# GenericCommand.net
KiCad netlist of a schematic drawn in EAGLE
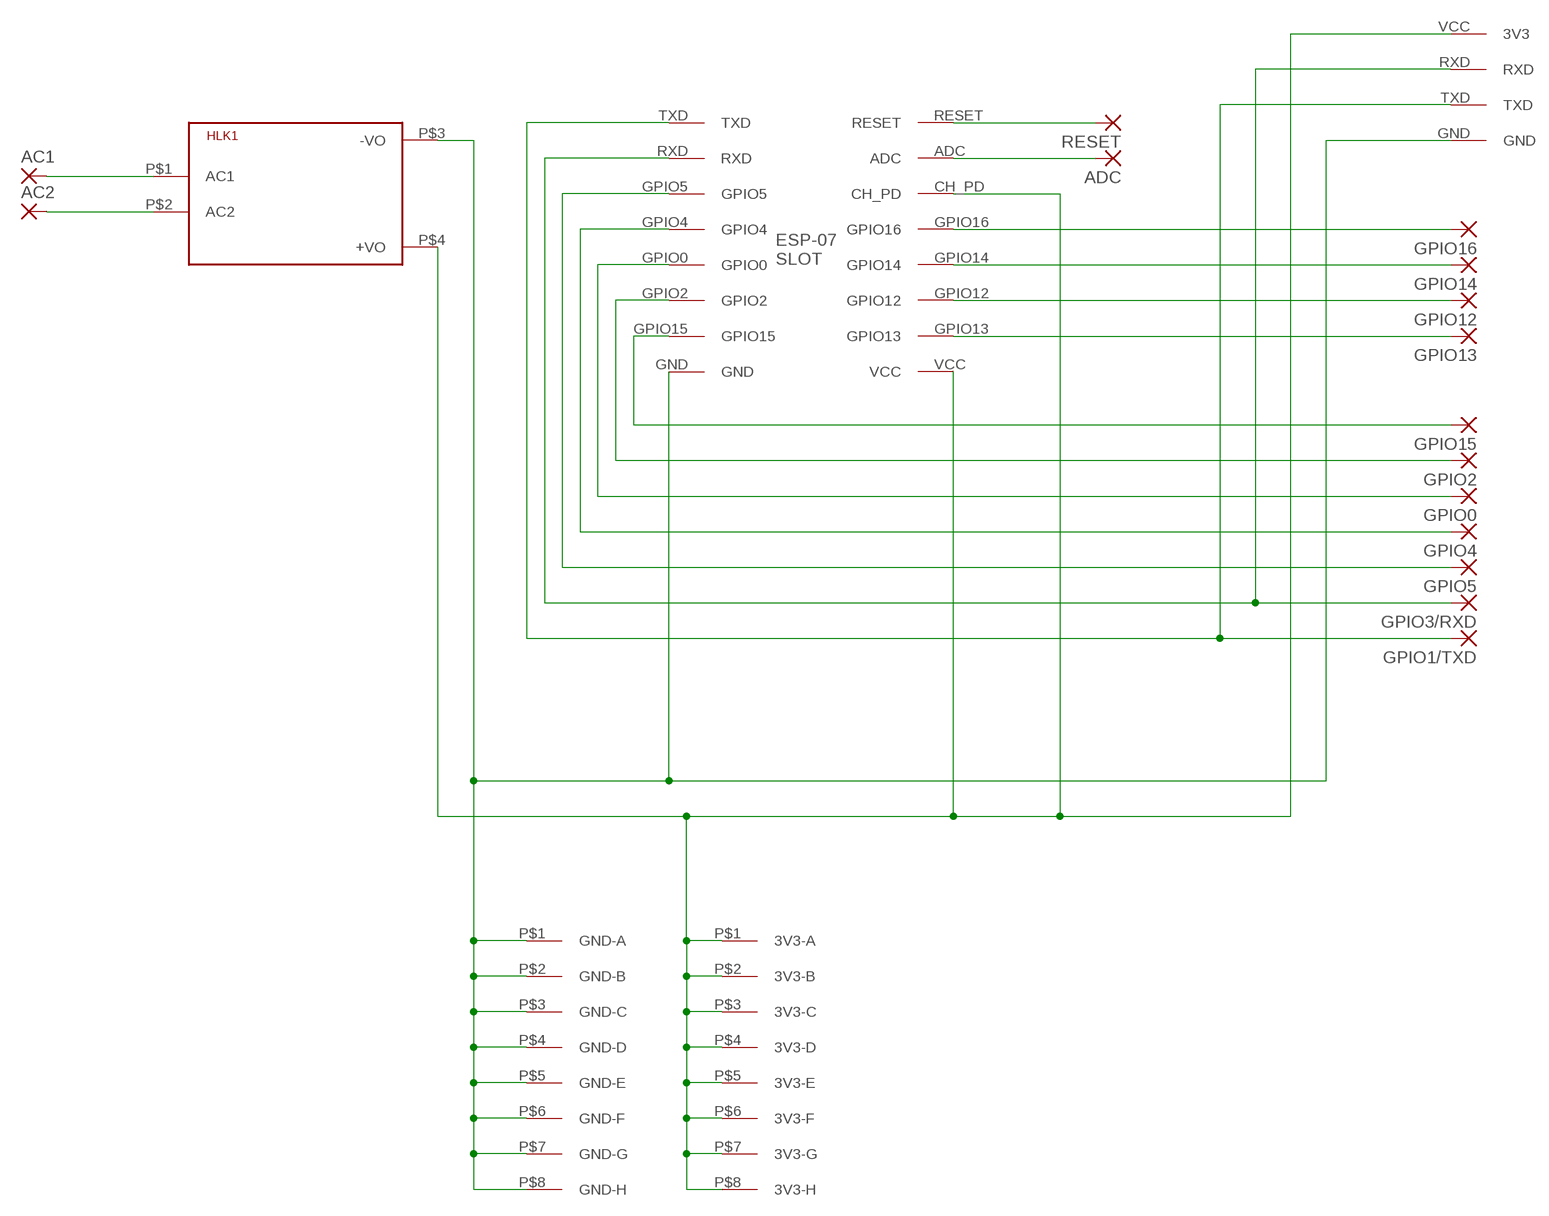
[diagram p0: schematic, sheet 1]

(export (version "E")
  (design (tool "Eeschema 10.0.6"))
  (components
    (comp (ref "AC1")
      (value "3,81/1,4")
      (footprint "eagle-import:3,81_1,4")
      (libsource (lib "eagle-import") (part "3,81/1,4"))
    )
    (comp (ref "AC2")
      (value "3,81/1,4")
      (footprint "eagle-import:3,81_1,4")
      (libsource (lib "eagle-import") (part "3,81/1,4"))
    )
    (comp (ref "ADC")
      (value "1,6/0,9")
      (footprint "eagle-import:1,6_0,9")
      (libsource (lib "eagle-import") (part "1,6/0,9"))
    )
    (comp (ref "GPIO0")
      (value "1,6/0,9")
      (footprint "eagle-import:1,6_0,9")
      (libsource (lib "eagle-import") (part "1,6/0,9"))
    )
    (comp (ref "GPIO1/TXD")
      (value "1,6/0,9")
      (footprint "eagle-import:1,6_0,9")
      (libsource (lib "eagle-import") (part "1,6/0,9"))
    )
    (comp (ref "GPIO2")
      (value "1,6/0,9")
      (footprint "eagle-import:1,6_0,9")
      (libsource (lib "eagle-import") (part "1,6/0,9"))
    )
    (comp (ref "GPIO3/RXD")
      (value "1,6/0,9")
      (footprint "eagle-import:1,6_0,9")
      (libsource (lib "eagle-import") (part "1,6/0,9"))
    )
    (comp (ref "GPIO4")
      (value "1,6/0,9")
      (footprint "eagle-import:1,6_0,9")
      (libsource (lib "eagle-import") (part "1,6/0,9"))
    )
    (comp (ref "GPIO5")
      (value "1,6/0,9")
      (footprint "eagle-import:1,6_0,9")
      (libsource (lib "eagle-import") (part "1,6/0,9"))
    )
    (comp (ref "GPIO12")
      (value "1,6/0,9")
      (footprint "eagle-import:1,6_0,9")
      (libsource (lib "eagle-import") (part "1,6/0,9"))
    )
    (comp (ref "GPIO13")
      (value "1,6/0,9")
      (footprint "eagle-import:1,6_0,9")
      (libsource (lib "eagle-import") (part "1,6/0,9"))
    )
    (comp (ref "GPIO14")
      (value "1,6/0,9")
      (footprint "eagle-import:1,6_0,9")
      (libsource (lib "eagle-import") (part "1,6/0,9"))
    )
    (comp (ref "GPIO15")
      (value "1,6/0,9")
      (footprint "eagle-import:1,6_0,9")
      (libsource (lib "eagle-import") (part "1,6/0,9"))
    )
    (comp (ref "GPIO16")
      (value "1,6/0,9")
      (footprint "eagle-import:1,6_0,9")
      (libsource (lib "eagle-import") (part "1,6/0,9"))
    )
    (comp (ref "HLK1")
      (value "HLK-PM013W")
      (footprint "eagle-import:HLK-PM01")
      (libsource (lib "eagle-import") (part "HLK-PM013W"))
    )
    (comp (ref "RESET")
      (value "1,6/0,9")
      (footprint "eagle-import:1,6_0,9")
      (libsource (lib "eagle-import") (part "1,6/0,9"))
    )
    (comp (ref "U$1")
      (value "ESP-07")
      (footprint "eagle-import:ESP-07")
      (libsource (lib "eagle-import") (part "ESP-07"))
    )
    (comp (ref "U$2")
      (value "CP-2102-CONN")
      (footprint "eagle-import:CP-2102-CONN")
      (libsource (lib "eagle-import") (part "CP-2102-CONN"))
    )
    (comp (ref "U$3")
      (value "3V3-8")
      (footprint "eagle-import:3.3V-8")
      (libsource (lib "eagle-import") (part "3V3-8"))
    )
    (comp (ref "U$4")
      (value "GND-8")
      (footprint "eagle-import:GND-8")
      (libsource (lib "eagle-import") (part "GND-8"))
    )
  )
  (nets
    (net (code "1") (name "Net-(AC1-P)") (class "Default")
      (node (ref "AC1") (pin "1") (pinfunction "P_1") (pintype "passive"))
      (node (ref "HLK1") (pin "P$1") (pinfunction "AC1_P$1") (pintype "bidirectional"))
    )
    (net (code "2") (name "Net-(AC2-P)") (class "Default")
      (node (ref "AC2") (pin "1") (pinfunction "P_1") (pintype "passive"))
      (node (ref "HLK1") (pin "P$2") (pinfunction "AC2_P$2") (pintype "bidirectional"))
    )
    (net (code "3") (name "Net-(ADC-P)") (class "Default")
      (node (ref "ADC") (pin "1") (pinfunction "P_1") (pintype "passive"))
      (node (ref "U$1") (pin "ADC") (pinfunction "ADC_ADC") (pintype "bidirectional"))
    )
    (net (code "4") (name "Net-(GPIO0-P)") (class "Default")
      (node (ref "GPIO0") (pin "1") (pinfunction "P_1") (pintype "passive"))
      (node (ref "U$1") (pin "GPIO0") (pinfunction "GPIO0_GPIO0") (pintype "bidirectional"))
    )
    (net (code "5") (name "Net-(GPIO1/TXD-P)") (class "Default")
      (node (ref "GPIO1/TXD") (pin "1") (pinfunction "P_1") (pintype "passive"))
      (node (ref "U$1") (pin "TXD") (pinfunction "TXD_TXD") (pintype "bidirectional"))
      (node (ref "U$2") (pin "TXD") (pinfunction "TXD_TXD") (pintype "bidirectional"))
    )
    (net (code "6") (name "Net-(GPIO2-P)") (class "Default")
      (node (ref "GPIO2") (pin "1") (pinfunction "P_1") (pintype "passive"))
      (node (ref "U$1") (pin "GPIO2") (pinfunction "GPIO2_GPIO2") (pintype "bidirectional"))
    )
    (net (code "7") (name "Net-(GPIO3/RXD-P)") (class "Default")
      (node (ref "GPIO3/RXD") (pin "1") (pinfunction "P_1") (pintype "passive"))
      (node (ref "U$1") (pin "RXD") (pinfunction "RXD_RXD") (pintype "bidirectional"))
      (node (ref "U$2") (pin "RXD") (pinfunction "RXD_RXD") (pintype "bidirectional"))
    )
    (net (code "8") (name "Net-(GPIO4-P)") (class "Default")
      (node (ref "GPIO4") (pin "1") (pinfunction "P_1") (pintype "passive"))
      (node (ref "U$1") (pin "GPIO4") (pinfunction "GPIO4_GPIO4") (pintype "bidirectional"))
    )
    (net (code "9") (name "Net-(GPIO5-P)") (class "Default")
      (node (ref "GPIO5") (pin "1") (pinfunction "P_1") (pintype "passive"))
      (node (ref "U$1") (pin "GPIO5") (pinfunction "GPIO5_GPIO5") (pintype "bidirectional"))
    )
    (net (code "10") (name "Net-(GPIO12-P)") (class "Default")
      (node (ref "GPIO12") (pin "1") (pinfunction "P_1") (pintype "passive"))
      (node (ref "U$1") (pin "GPIO12") (pinfunction "GPIO12_GPIO12") (pintype "bidirectional"))
    )
    (net (code "11") (name "Net-(GPIO13-P)") (class "Default")
      (node (ref "GPIO13") (pin "1") (pinfunction "P_1") (pintype "passive"))
      (node (ref "U$1") (pin "GPIO13") (pinfunction "GPIO13_GPIO13") (pintype "bidirectional"))
    )
    (net (code "12") (name "Net-(GPIO14-P)") (class "Default")
      (node (ref "GPIO14") (pin "1") (pinfunction "P_1") (pintype "passive"))
      (node (ref "U$1") (pin "GPIO14") (pinfunction "GPIO14_GPIO14") (pintype "bidirectional"))
    )
    (net (code "13") (name "Net-(GPIO15-P)") (class "Default")
      (node (ref "GPIO15") (pin "1") (pinfunction "P_1") (pintype "passive"))
      (node (ref "U$1") (pin "GPIO15") (pinfunction "GPIO15_GPIO15") (pintype "bidirectional"))
    )
    (net (code "14") (name "Net-(GPIO16-P)") (class "Default")
      (node (ref "GPIO16") (pin "1") (pinfunction "P_1") (pintype "passive"))
      (node (ref "U$1") (pin "GPIO16") (pinfunction "GPIO16_GPIO16") (pintype "bidirectional"))
    )
    (net (code "15") (name "Net-(HLK1-+VO)") (class "Default")
      (node (ref "HLK1") (pin "P$4") (pinfunction "+VO_P$4") (pintype "bidirectional"))
      (node (ref "U$1") (pin "CH_PD") (pinfunction "CH_PD_CH_PD") (pintype "bidirectional"))
      (node (ref "U$1") (pin "VCC") (pinfunction "VCC_VCC") (pintype "bidirectional"))
      (node (ref "U$2") (pin "VCC") (pinfunction "3V3_VCC") (pintype "bidirectional"))
      (node (ref "U$3") (pin "P$1") (pinfunction "3V3-A_P$1") (pintype "bidirectional"))
      (node (ref "U$3") (pin "P$2") (pinfunction "3V3-B_P$2") (pintype "bidirectional"))
      (node (ref "U$3") (pin "P$3") (pinfunction "3V3-C_P$3") (pintype "bidirectional"))
      (node (ref "U$3") (pin "P$4") (pinfunction "3V3-D_P$4") (pintype "bidirectional"))
      (node (ref "U$3") (pin "P$5") (pinfunction "3V3-E_P$5") (pintype "bidirectional"))
      (node (ref "U$3") (pin "P$6") (pinfunction "3V3-F_P$6") (pintype "bidirectional"))
      (node (ref "U$3") (pin "P$7") (pinfunction "3V3-G_P$7") (pintype "bidirectional"))
      (node (ref "U$3") (pin "P$8") (pinfunction "3V3-H_P$8") (pintype "bidirectional"))
    )
    (net (code "16") (name "Net-(HLK1--VO)") (class "Default")
      (node (ref "HLK1") (pin "P$3") (pinfunction "-VO_P$3") (pintype "bidirectional"))
      (node (ref "U$1") (pin "GND") (pinfunction "GND_GND") (pintype "bidirectional"))
      (node (ref "U$2") (pin "GND") (pinfunction "GND_GND") (pintype "bidirectional"))
      (node (ref "U$4") (pin "P$1") (pinfunction "GND-A_P$1") (pintype "bidirectional"))
      (node (ref "U$4") (pin "P$2") (pinfunction "GND-B_P$2") (pintype "bidirectional"))
      (node (ref "U$4") (pin "P$3") (pinfunction "GND-C_P$3") (pintype "bidirectional"))
      (node (ref "U$4") (pin "P$4") (pinfunction "GND-D_P$4") (pintype "bidirectional"))
      (node (ref "U$4") (pin "P$5") (pinfunction "GND-E_P$5") (pintype "bidirectional"))
      (node (ref "U$4") (pin "P$6") (pinfunction "GND-F_P$6") (pintype "bidirectional"))
      (node (ref "U$4") (pin "P$7") (pinfunction "GND-G_P$7") (pintype "bidirectional"))
      (node (ref "U$4") (pin "P$8") (pinfunction "GND-H_P$8") (pintype "bidirectional"))
    )
    (net (code "17") (name "Net-(RESET-P)") (class "Default")
      (node (ref "RESET") (pin "1") (pinfunction "P_1") (pintype "passive"))
      (node (ref "U$1") (pin "RESET") (pinfunction "RESET_RESET") (pintype "bidirectional"))
    )
  )
)
